# schema_test_week_5.net
KiCad netlist of a schematic drawn in EAGLE
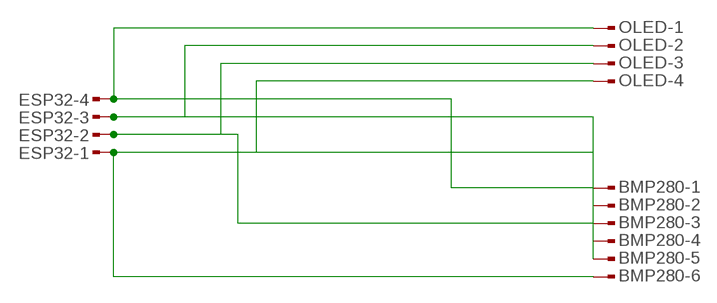
[diagram p0: schematic, sheet 1]

(export (version "E")
  (design (tool "Eeschema 10.0.6"))
  (components
    (comp (ref "BMP280")
      (value "MTOP-6")
      (footprint "eagle-import:MTOP-6")
      (libsource (lib "eagle-import") (part "MTOP-6"))
    )
    (comp (ref "ESP32")
      (value "MTOP-4")
      (footprint "eagle-import:MTOP-4")
      (libsource (lib "eagle-import") (part "MTOP-4"))
    )
    (comp (ref "OLED")
      (value "MTOP-4")
      (footprint "eagle-import:MTOP-4")
      (libsource (lib "eagle-import") (part "MTOP-4"))
    )
  )
  (nets
    (net (code "1") (name "Net-(BMP280B-1)") (class "Default")
      (node (ref "BMP280") (pin "2") (pinfunction "1_2") (pintype "passive"))
      (node (ref "ESP32") (pin "3") (pinfunction "1_3") (pintype "passive"))
      (node (ref "OLED") (pin "2") (pinfunction "1_2") (pintype "passive"))
    )
    (net (code "2") (name "Net-(BMP280C-1)") (class "Default")
      (node (ref "BMP280") (pin "3") (pinfunction "1_3") (pintype "passive"))
      (node (ref "ESP32") (pin "2") (pinfunction "1_2") (pintype "passive"))
      (node (ref "OLED") (pin "3") (pinfunction "1_3") (pintype "passive"))
    )
    (net (code "3") (name "Net-(BMP280D-1)") (class "Default")
      (node (ref "BMP280") (pin "4") (pinfunction "1_4") (pintype "passive"))
      (node (ref "BMP280") (pin "5") (pinfunction "1_5") (pintype "passive"))
      (node (ref "BMP280") (pin "6") (pinfunction "1_6") (pintype "passive"))
      (node (ref "ESP32") (pin "1") (pinfunction "1_1") (pintype "passive"))
      (node (ref "OLED") (pin "4") (pinfunction "1_4") (pintype "passive"))
    )
    (net (code "4") (name "Net-(ESP32D-1)") (class "Default")
      (node (ref "BMP280") (pin "1") (pinfunction "1_1") (pintype "passive"))
      (node (ref "ESP32") (pin "4") (pinfunction "1_4") (pintype "passive"))
      (node (ref "OLED") (pin "1") (pinfunction "1_1") (pintype "passive"))
    )
  )
)
